# schematic.net
KiCad netlist of a schematic drawn in EAGLE
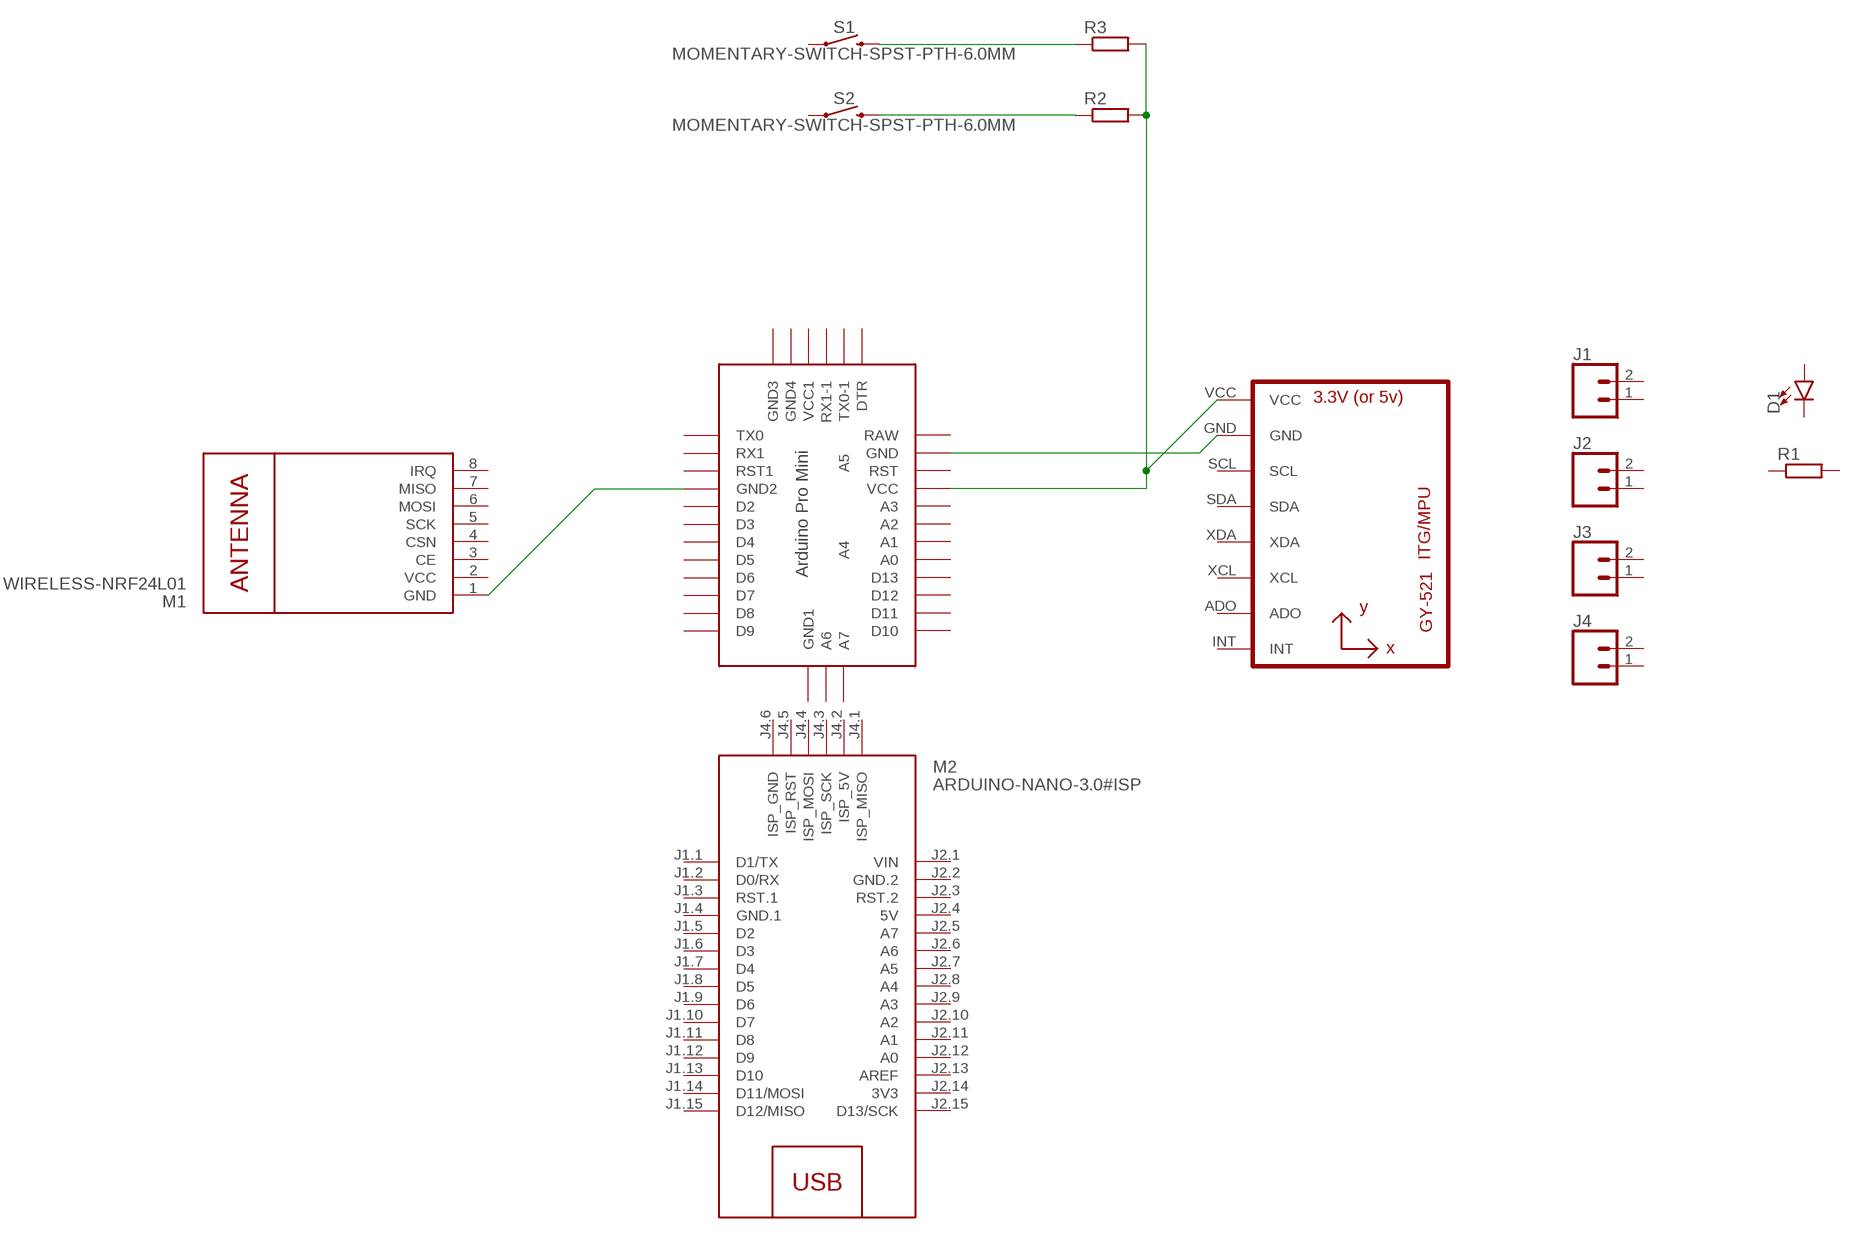
[diagram p0: schematic, sheet 1]

(export (version "E")
  (design (tool "Eeschema 10.0.6"))
  (components
    (comp (ref "D1")
      (value "LED3MM")
      (footprint "eagle-import:LED_3MM")
      (libsource (lib "eagle-import") (part "LED3MM"))
    )
    (comp (ref "J1")
      (value "CONN_02LOCK")
      (footprint "eagle-import:1X02_LOCK")
      (libsource (lib "eagle-import") (part "CONN_02LOCK"))
    )
    (comp (ref "J2")
      (value "CONN_02LOCK")
      (footprint "eagle-import:1X02_LOCK")
      (libsource (lib "eagle-import") (part "CONN_02LOCK"))
    )
    (comp (ref "J3")
      (value "CONN_02LOCK")
      (footprint "eagle-import:1X02_LOCK")
      (libsource (lib "eagle-import") (part "CONN_02LOCK"))
    )
    (comp (ref "J4")
      (value "CONN_02LOCK")
      (footprint "eagle-import:1X02_LOCK")
      (libsource (lib "eagle-import") (part "CONN_02LOCK"))
    )
    (comp (ref "M1")
      (value "WIRELESS-NRF24L01")
      (footprint "eagle-import:WIRELESS-NRF24L01")
      (libsource (lib "eagle-import") (part "WIRELESS-NRF24L01"))
    )
    (comp (ref "M2")
      (value "ARDUINO-NANO-3.0#ISP")
      (footprint "eagle-import:ARDUINO-NANO-3.0#ISP")
      (libsource (lib "eagle-import") (part "ARDUINO-NANO-3.0#ISP"))
    )
    (comp (ref "R1")
      (value "R-EU_0207/10")
      (footprint "eagle-import:0207_10")
      (libsource (lib "eagle-import") (part "R-EU_0207/10"))
    )
    (comp (ref "R2")
      (value "R-EU_0207/10")
      (footprint "eagle-import:0207_10")
      (libsource (lib "eagle-import") (part "R-EU_0207/10"))
    )
    (comp (ref "R3")
      (value "R-EU_0207/10")
      (footprint "eagle-import:0207_10")
      (libsource (lib "eagle-import") (part "R-EU_0207/10"))
    )
    (comp (ref "S1")
      (value "MOMENTARY-SWITCH-SPST-PTH-6.0MM")
      (footprint "eagle-import:TACTILE_SWITCH_PTH_6.0MM")
      (libsource (lib "eagle-import") (part "MOMENTARY-SWITCH-SPST-PTH-6.0MM"))
    )
    (comp (ref "S2")
      (value "MOMENTARY-SWITCH-SPST-PTH-6.0MM")
      (footprint "eagle-import:TACTILE_SWITCH_PTH_6.0MM")
      (libsource (lib "eagle-import") (part "MOMENTARY-SWITCH-SPST-PTH-6.0MM"))
    )
    (comp (ref "U$1")
      (value "ABK-PRO-MINI")
      (footprint "eagle-import:ABK-PRO-MINI")
      (libsource (lib "eagle-import") (part "ABK-PRO-MINI"))
    )
    (comp (ref "U1")
      (value "GY-521MPU6050")
      (footprint "eagle-import:GY-521")
      (libsource (lib "eagle-import") (part "GY-521MPU6050"))
    )
  )
  (nets
    (net (code "1") (name "/3V3") (class "Default")
      (node (ref "M2") (pin "J2.14") (pinfunction "3V3_J2.14") (pintype "power_in"))
    )
    (net (code "2") (name "/5V") (class "Default")
      (node (ref "M2") (pin "J2.4") (pinfunction "5V_J2.4") (pintype "power_in"))
    )
    (net (code "3") (name "/GND.1") (class "Default")
      (node (ref "M2") (pin "J1.4") (pinfunction "GND.1_J1.4") (pintype "power_in"))
    )
    (net (code "4") (name "/GND.2") (class "Default")
      (node (ref "M2") (pin "J2.2") (pinfunction "GND.2_J2.2") (pintype "power_in"))
    )
    (net (code "5") (name "/VCC") (class "Default")
      (node (ref "M1") (pin "2") (pinfunction "VCC_2") (pintype "power_in"))
    )
    (net (code "6") (name "/VIN") (class "Default")
      (node (ref "M2") (pin "J2.1") (pinfunction "VIN_J2.1") (pintype "power_in"))
    )
    (net (code "7") (name "Net-(M1-GND)") (class "Default")
      (node (ref "M1") (pin "1") (pinfunction "GND_1") (pintype "power_in"))
      (node (ref "U$1") (pin "GND1") (pinfunction "GND2_GND1") (pintype "bidirectional"))
    )
    (net (code "8") (name "Net-(R2-Pad2)") (class "Default")
      (node (ref "R2") (pin "2") (pinfunction "2_2") (pintype "passive"))
      (node (ref "R3") (pin "2") (pinfunction "2_2") (pintype "passive"))
      (node (ref "U$1") (pin "VCC") (pinfunction "VCC_VCC") (pintype "bidirectional"))
      (node (ref "U1") (pin "VCC") (pinfunction "VCC_VCC") (pintype "bidirectional"))
    )
    (net (code "9") (name "Net-(S1-2)") (class "Default")
      (node (ref "R3") (pin "1") (pinfunction "1_1") (pintype "passive"))
      (node (ref "S1") (pin "3") (pinfunction "2_3") (pintype "passive"))
    )
    (net (code "10") (name "Net-(S2-2)") (class "Default")
      (node (ref "R2") (pin "1") (pinfunction "1_1") (pintype "passive"))
      (node (ref "S2") (pin "3") (pinfunction "2_3") (pintype "passive"))
    )
    (net (code "11") (name "Net-(U$1-PadGND)") (class "Default")
      (node (ref "U$1") (pin "GND") (pinfunction "GND_GND") (pintype "bidirectional"))
      (node (ref "U1") (pin "GND") (pinfunction "GND_GND") (pintype "bidirectional"))
    )
    (net (code "12") (name "unconnected-(D1-C-PadK)") (class "Default")
      (node (ref "D1") (pin "K") (pinfunction "C_K") (pintype "passive"))
    )
    (net (code "13") (name "unconnected-(D1-PadA)") (class "Default")
      (node (ref "D1") (pin "A") (pinfunction "A_A") (pintype "passive"))
    )
    (net (code "14") (name "unconnected-(J1-Pad1)") (class "Default")
      (node (ref "J1") (pin "1") (pinfunction "1_1") (pintype "passive"))
    )
    (net (code "15") (name "unconnected-(J1-Pad2)") (class "Default")
      (node (ref "J1") (pin "2") (pinfunction "2_2") (pintype "passive"))
    )
    (net (code "16") (name "unconnected-(J2-Pad1)") (class "Default")
      (node (ref "J2") (pin "1") (pinfunction "1_1") (pintype "passive"))
    )
    (net (code "17") (name "unconnected-(J2-Pad2)") (class "Default")
      (node (ref "J2") (pin "2") (pinfunction "2_2") (pintype "passive"))
    )
    (net (code "18") (name "unconnected-(J3-Pad1)") (class "Default")
      (node (ref "J3") (pin "1") (pinfunction "1_1") (pintype "passive"))
    )
    (net (code "19") (name "unconnected-(J3-Pad2)") (class "Default")
      (node (ref "J3") (pin "2") (pinfunction "2_2") (pintype "passive"))
    )
    (net (code "20") (name "unconnected-(J4-Pad1)") (class "Default")
      (node (ref "J4") (pin "1") (pinfunction "1_1") (pintype "passive"))
    )
    (net (code "21") (name "unconnected-(J4-Pad2)") (class "Default")
      (node (ref "J4") (pin "2") (pinfunction "2_2") (pintype "passive"))
    )
    (net (code "22") (name "unconnected-(M1-CE-Pad3)") (class "Default")
      (node (ref "M1") (pin "3") (pinfunction "CE_3") (pintype "bidirectional"))
    )
    (net (code "23") (name "unconnected-(M1-CSN-Pad4)") (class "Default")
      (node (ref "M1") (pin "4") (pinfunction "CSN_4") (pintype "bidirectional"))
    )
    (net (code "24") (name "unconnected-(M1-IRQ-Pad8)") (class "Default")
      (node (ref "M1") (pin "8") (pinfunction "IRQ_8") (pintype "bidirectional"))
    )
    (net (code "25") (name "unconnected-(M1-MISO-Pad7)") (class "Default")
      (node (ref "M1") (pin "7") (pinfunction "MISO_7") (pintype "bidirectional"))
    )
    (net (code "26") (name "unconnected-(M1-MOSI-Pad6)") (class "Default")
      (node (ref "M1") (pin "6") (pinfunction "MOSI_6") (pintype "bidirectional"))
    )
    (net (code "27") (name "unconnected-(M1-SCK-Pad5)") (class "Default")
      (node (ref "M1") (pin "5") (pinfunction "SCK_5") (pintype "bidirectional"))
    )
    (net (code "28") (name "unconnected-(M2-A0-PadJ2.12)") (class "Default")
      (node (ref "M2") (pin "J2.12") (pinfunction "A0_J2.12") (pintype "bidirectional"))
    )
    (net (code "29") (name "unconnected-(M2-A1-PadJ2.11)") (class "Default")
      (node (ref "M2") (pin "J2.11") (pinfunction "A1_J2.11") (pintype "bidirectional"))
    )
    (net (code "30") (name "unconnected-(M2-A2-PadJ2.10)") (class "Default")
      (node (ref "M2") (pin "J2.10") (pinfunction "A2_J2.10") (pintype "bidirectional"))
    )
    (net (code "31") (name "unconnected-(M2-A3-PadJ2.9)") (class "Default")
      (node (ref "M2") (pin "J2.9") (pinfunction "A3_J2.9") (pintype "bidirectional"))
    )
    (net (code "32") (name "unconnected-(M2-A4-PadJ2.8)") (class "Default")
      (node (ref "M2") (pin "J2.8") (pinfunction "A4_J2.8") (pintype "bidirectional"))
    )
    (net (code "33") (name "unconnected-(M2-A5-PadJ2.7)") (class "Default")
      (node (ref "M2") (pin "J2.7") (pinfunction "A5_J2.7") (pintype "bidirectional"))
    )
    (net (code "34") (name "unconnected-(M2-A6-PadJ2.6)") (class "Default")
      (node (ref "M2") (pin "J2.6") (pinfunction "A6_J2.6") (pintype "bidirectional"))
    )
    (net (code "35") (name "unconnected-(M2-A7-PadJ2.5)") (class "Default")
      (node (ref "M2") (pin "J2.5") (pinfunction "A7_J2.5") (pintype "bidirectional"))
    )
    (net (code "36") (name "unconnected-(M2-AREF-PadJ2.13)") (class "Default")
      (node (ref "M2") (pin "J2.13") (pinfunction "AREF_J2.13") (pintype "bidirectional"))
    )
    (net (code "37") (name "unconnected-(M2-D0{slash}RX-PadJ1.2)") (class "Default")
      (node (ref "M2") (pin "J1.2") (pinfunction "D0/RX_J1.2") (pintype "bidirectional"))
    )
    (net (code "38") (name "unconnected-(M2-D1{slash}TX-PadJ1.1)") (class "Default")
      (node (ref "M2") (pin "J1.1") (pinfunction "D1/TX_J1.1") (pintype "bidirectional"))
    )
    (net (code "39") (name "unconnected-(M2-D2-PadJ1.5)") (class "Default")
      (node (ref "M2") (pin "J1.5") (pinfunction "D2_J1.5") (pintype "bidirectional"))
    )
    (net (code "40") (name "unconnected-(M2-D3-PadJ1.6)") (class "Default")
      (node (ref "M2") (pin "J1.6") (pinfunction "D3_J1.6") (pintype "bidirectional"))
    )
    (net (code "41") (name "unconnected-(M2-D4-PadJ1.7)") (class "Default")
      (node (ref "M2") (pin "J1.7") (pinfunction "D4_J1.7") (pintype "bidirectional"))
    )
    (net (code "42") (name "unconnected-(M2-D5-PadJ1.8)") (class "Default")
      (node (ref "M2") (pin "J1.8") (pinfunction "D5_J1.8") (pintype "bidirectional"))
    )
    (net (code "43") (name "unconnected-(M2-D6-PadJ1.9)") (class "Default")
      (node (ref "M2") (pin "J1.9") (pinfunction "D6_J1.9") (pintype "bidirectional"))
    )
    (net (code "44") (name "unconnected-(M2-D7-PadJ1.10)") (class "Default")
      (node (ref "M2") (pin "J1.10") (pinfunction "D7_J1.10") (pintype "bidirectional"))
    )
    (net (code "45") (name "unconnected-(M2-D8-PadJ1.11)") (class "Default")
      (node (ref "M2") (pin "J1.11") (pinfunction "D8_J1.11") (pintype "bidirectional"))
    )
    (net (code "46") (name "unconnected-(M2-D9-PadJ1.12)") (class "Default")
      (node (ref "M2") (pin "J1.12") (pinfunction "D9_J1.12") (pintype "bidirectional"))
    )
    (net (code "47") (name "unconnected-(M2-D10-PadJ1.13)") (class "Default")
      (node (ref "M2") (pin "J1.13") (pinfunction "D10_J1.13") (pintype "bidirectional"))
    )
    (net (code "48") (name "unconnected-(M2-D11{slash}MOSI-PadJ1.14)") (class "Default")
      (node (ref "M2") (pin "J1.14") (pinfunction "D11/MOSI_J1.14") (pintype "bidirectional"))
    )
    (net (code "49") (name "unconnected-(M2-D12{slash}MISO-PadJ1.15)") (class "Default")
      (node (ref "M2") (pin "J1.15") (pinfunction "D12/MISO_J1.15") (pintype "bidirectional"))
    )
    (net (code "50") (name "unconnected-(M2-D13{slash}SCK-PadJ2.15)") (class "Default")
      (node (ref "M2") (pin "J2.15") (pinfunction "D13/SCK_J2.15") (pintype "bidirectional"))
    )
    (net (code "51") (name "unconnected-(M2-ISP_5V-PadJ4.2)") (class "Default")
      (node (ref "M2") (pin "J4.2") (pinfunction "ISP_5V_J4.2") (pintype "bidirectional"))
    )
    (net (code "52") (name "unconnected-(M2-ISP_GND-PadJ4.6)") (class "Default")
      (node (ref "M2") (pin "J4.6") (pinfunction "ISP_GND_J4.6") (pintype "bidirectional"))
    )
    (net (code "53") (name "unconnected-(M2-ISP_MISO-PadJ4.1)") (class "Default")
      (node (ref "M2") (pin "J4.1") (pinfunction "ISP_MISO_J4.1") (pintype "bidirectional"))
    )
    (net (code "54") (name "unconnected-(M2-ISP_MOSI-PadJ4.4)") (class "Default")
      (node (ref "M2") (pin "J4.4") (pinfunction "ISP_MOSI_J4.4") (pintype "bidirectional"))
    )
    (net (code "55") (name "unconnected-(M2-ISP_RST-PadJ4.5)") (class "Default")
      (node (ref "M2") (pin "J4.5") (pinfunction "ISP_RST_J4.5") (pintype "bidirectional"))
    )
    (net (code "56") (name "unconnected-(M2-ISP_SCK-PadJ4.3)") (class "Default")
      (node (ref "M2") (pin "J4.3") (pinfunction "ISP_SCK_J4.3") (pintype "bidirectional"))
    )
    (net (code "57") (name "unconnected-(M2-RST.1-PadJ1.3)") (class "Default")
      (node (ref "M2") (pin "J1.3") (pinfunction "RST.1_J1.3") (pintype "bidirectional"))
    )
    (net (code "58") (name "unconnected-(M2-RST.2-PadJ2.3)") (class "Default")
      (node (ref "M2") (pin "J2.3") (pinfunction "RST.2_J2.3") (pintype "bidirectional"))
    )
    (net (code "59") (name "unconnected-(R1-Pad1)") (class "Default")
      (node (ref "R1") (pin "1") (pinfunction "1_1") (pintype "passive"))
    )
    (net (code "60") (name "unconnected-(R1-Pad2)") (class "Default")
      (node (ref "R1") (pin "2") (pinfunction "2_2") (pintype "passive"))
    )
    (net (code "61") (name "unconnected-(S1-Pad1)") (class "Default")
      (node (ref "S1") (pin "1") (pinfunction "1_1") (pintype "passive"))
    )
    (net (code "62") (name "unconnected-(S2-Pad1)") (class "Default")
      (node (ref "S2") (pin "1") (pinfunction "1_1") (pintype "passive"))
    )
    (net (code "63") (name "unconnected-(U$1-GND1-PadGND4)") (class "Default")
      (node (ref "U$1") (pin "GND4") (pinfunction "GND1_GND4") (pintype "bidirectional"))
    )
    (net (code "64") (name "unconnected-(U$1-GND3-PadGND2)") (class "Default")
      (node (ref "U$1") (pin "GND2") (pinfunction "GND3_GND2") (pintype "bidirectional"))
    )
    (net (code "65") (name "unconnected-(U$1-GND4-PadGND3)") (class "Default")
      (node (ref "U$1") (pin "GND3") (pinfunction "GND4_GND3") (pintype "bidirectional"))
    )
    (net (code "66") (name "unconnected-(U$1-PadA0)") (class "Default")
      (node (ref "U$1") (pin "A0") (pinfunction "A0_A0") (pintype "bidirectional"))
    )
    (net (code "67") (name "unconnected-(U$1-PadA1)") (class "Default")
      (node (ref "U$1") (pin "A1") (pinfunction "A1_A1") (pintype "bidirectional"))
    )
    (net (code "68") (name "unconnected-(U$1-PadA2)") (class "Default")
      (node (ref "U$1") (pin "A2") (pinfunction "A2_A2") (pintype "bidirectional"))
    )
    (net (code "69") (name "unconnected-(U$1-PadA3)") (class "Default")
      (node (ref "U$1") (pin "A3") (pinfunction "A3_A3") (pintype "bidirectional"))
    )
    (net (code "70") (name "unconnected-(U$1-PadA4)") (class "Default")
      (node (ref "U$1") (pin "A4") (pinfunction "A4_A4") (pintype "bidirectional"))
    )
    (net (code "71") (name "unconnected-(U$1-PadA5)") (class "Default")
      (node (ref "U$1") (pin "A5") (pinfunction "A5_A5") (pintype "bidirectional"))
    )
    (net (code "72") (name "unconnected-(U$1-PadA6)") (class "Default")
      (node (ref "U$1") (pin "A6") (pinfunction "A6_A6") (pintype "bidirectional"))
    )
    (net (code "73") (name "unconnected-(U$1-PadA7)") (class "Default")
      (node (ref "U$1") (pin "A7") (pinfunction "A7_A7") (pintype "bidirectional"))
    )
    (net (code "74") (name "unconnected-(U$1-PadD2)") (class "Default")
      (node (ref "U$1") (pin "D2") (pinfunction "D2_D2") (pintype "bidirectional"))
    )
    (net (code "75") (name "unconnected-(U$1-PadD3)") (class "Default")
      (node (ref "U$1") (pin "D3") (pinfunction "D3_D3") (pintype "bidirectional"))
    )
    (net (code "76") (name "unconnected-(U$1-PadD4)") (class "Default")
      (node (ref "U$1") (pin "D4") (pinfunction "D4_D4") (pintype "bidirectional"))
    )
    (net (code "77") (name "unconnected-(U$1-PadD5)") (class "Default")
      (node (ref "U$1") (pin "D5") (pinfunction "D5_D5") (pintype "bidirectional"))
    )
    (net (code "78") (name "unconnected-(U$1-PadD6)") (class "Default")
      (node (ref "U$1") (pin "D6") (pinfunction "D6_D6") (pintype "bidirectional"))
    )
    (net (code "79") (name "unconnected-(U$1-PadD7)") (class "Default")
      (node (ref "U$1") (pin "D7") (pinfunction "D7_D7") (pintype "bidirectional"))
    )
    (net (code "80") (name "unconnected-(U$1-PadD8)") (class "Default")
      (node (ref "U$1") (pin "D8") (pinfunction "D8_D8") (pintype "bidirectional"))
    )
    (net (code "81") (name "unconnected-(U$1-PadD9)") (class "Default")
      (node (ref "U$1") (pin "D9") (pinfunction "D9_D9") (pintype "bidirectional"))
    )
    (net (code "82") (name "unconnected-(U$1-PadD10)") (class "Default")
      (node (ref "U$1") (pin "D10") (pinfunction "D10_D10") (pintype "bidirectional"))
    )
    (net (code "83") (name "unconnected-(U$1-PadD11)") (class "Default")
      (node (ref "U$1") (pin "D11") (pinfunction "D11_D11") (pintype "bidirectional"))
    )
    (net (code "84") (name "unconnected-(U$1-PadD12)") (class "Default")
      (node (ref "U$1") (pin "D12") (pinfunction "D12_D12") (pintype "bidirectional"))
    )
    (net (code "85") (name "unconnected-(U$1-PadD13)") (class "Default")
      (node (ref "U$1") (pin "D13") (pinfunction "D13_D13") (pintype "bidirectional"))
    )
    (net (code "86") (name "unconnected-(U$1-PadDTR)") (class "Default")
      (node (ref "U$1") (pin "DTR") (pinfunction "DTR_DTR") (pintype "bidirectional"))
    )
    (net (code "87") (name "unconnected-(U$1-PadRAW)") (class "Default")
      (node (ref "U$1") (pin "RAW") (pinfunction "RAW_RAW") (pintype "bidirectional"))
    )
    (net (code "88") (name "unconnected-(U$1-PadRST)") (class "Default")
      (node (ref "U$1") (pin "RST") (pinfunction "RST_RST") (pintype "bidirectional"))
    )
    (net (code "89") (name "unconnected-(U$1-PadRST1)") (class "Default")
      (node (ref "U$1") (pin "RST1") (pinfunction "RST1_RST1") (pintype "bidirectional"))
    )
    (net (code "90") (name "unconnected-(U$1-PadRX1)") (class "Default")
      (node (ref "U$1") (pin "RX1") (pinfunction "RX1_RX1") (pintype "bidirectional"))
    )
    (net (code "91") (name "unconnected-(U$1-PadRX1-1)") (class "Default")
      (node (ref "U$1") (pin "RX1-1") (pinfunction "RX1-1_RX1-1") (pintype "bidirectional"))
    )
    (net (code "92") (name "unconnected-(U$1-PadTX0)") (class "Default")
      (node (ref "U$1") (pin "TX0") (pinfunction "TX0_TX0") (pintype "bidirectional"))
    )
    (net (code "93") (name "unconnected-(U$1-PadTX0-1)") (class "Default")
      (node (ref "U$1") (pin "TX0-1") (pinfunction "TX0-1_TX0-1") (pintype "bidirectional"))
    )
    (net (code "94") (name "unconnected-(U$1-PadVCC1)") (class "Default")
      (node (ref "U$1") (pin "VCC1") (pinfunction "VCC1_VCC1") (pintype "bidirectional"))
    )
    (net (code "95") (name "unconnected-(U1-PadADO)") (class "Default")
      (node (ref "U1") (pin "ADO") (pinfunction "ADO_ADO") (pintype "bidirectional"))
    )
    (net (code "96") (name "unconnected-(U1-PadINT)") (class "Default")
      (node (ref "U1") (pin "INT") (pinfunction "INT_INT") (pintype "bidirectional"))
    )
    (net (code "97") (name "unconnected-(U1-PadSCL)") (class "Default")
      (node (ref "U1") (pin "SCL") (pinfunction "SCL_SCL") (pintype "bidirectional"))
    )
    (net (code "98") (name "unconnected-(U1-PadSDA)") (class "Default")
      (node (ref "U1") (pin "SDA") (pinfunction "SDA_SDA") (pintype "bidirectional"))
    )
    (net (code "99") (name "unconnected-(U1-PadXCL)") (class "Default")
      (node (ref "U1") (pin "XCL") (pinfunction "XCL_XCL") (pintype "bidirectional"))
    )
    (net (code "100") (name "unconnected-(U1-PadXDA)") (class "Default")
      (node (ref "U1") (pin "XDA") (pinfunction "XDA_XDA") (pintype "bidirectional"))
    )
  )
)
